# Bluetooth.net
KiCad netlist of a schematic drawn in Altium Designer
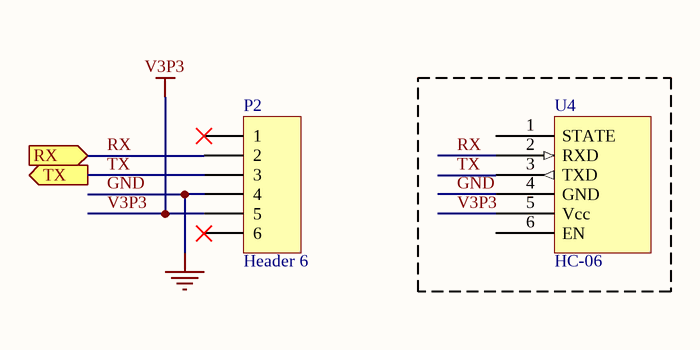
[diagram p0: Bluetooth.SchDoc]

(export (version "E")
  (design (tool "Eeschema 10.0.6"))
  (components
    (comp (ref "P2")
      (value "Header 6")
      (footprint "Header 6")
      (description "Header, 6-Pin")
      (libsource (lib "Miscellaneous Connectors") (part "Header 6"))
    )
    (comp (ref "U4") (value "HC-06") (description "Bluetooth") (libsource (lib "Components") (part "HC-06")))
  )
  (nets
    (net (code "1") (name "/RX") (class "Default")
      (node (ref "P2") (pin "2") (pinfunction "2_2") (pintype "passive"))
      (node (ref "U4") (pin "2") (pinfunction "RXD_2") (pintype "input"))
    )
    (net (code "2") (name "/TX") (class "Default")
      (node (ref "P2") (pin "3") (pinfunction "3_3") (pintype "passive"))
      (node (ref "U4") (pin "3") (pinfunction "TXD_3") (pintype "output"))
    )
    (net (code "3") (name "GND") (class "Default")
      (node (ref "P2") (pin "4") (pinfunction "4_4") (pintype "passive"))
      (node (ref "U4") (pin "4") (pinfunction "GND_4") (pintype "passive"))
    )
    (net (code "4") (name "V3P3") (class "Default")
      (node (ref "P2") (pin "5") (pinfunction "5_5") (pintype "passive"))
      (node (ref "U4") (pin "5") (pinfunction "Vcc_5") (pintype "power_in"))
    )
    (net (code "5") (name "unconnected-(P2-Pad1)") (class "Default")
      (node (ref "P2") (pin "1") (pinfunction "1_1") (pintype "passive+no_connect"))
    )
    (net (code "6") (name "unconnected-(P2-Pad6)") (class "Default")
      (node (ref "P2") (pin "6") (pinfunction "6_6") (pintype "passive+no_connect"))
    )
    (net (code "7") (name "unconnected-(U4-EN-Pad6)") (class "Default")
      (node (ref "U4") (pin "6") (pinfunction "EN_6") (pintype "passive"))
    )
    (net (code "8") (name "unconnected-(U4-STATE-Pad1)") (class "Default")
      (node (ref "U4") (pin "1") (pinfunction "STATE_1") (pintype "passive"))
    )
  )
)
